# 3V3.net
KiCad netlist of a schematic drawn in Altium Designer
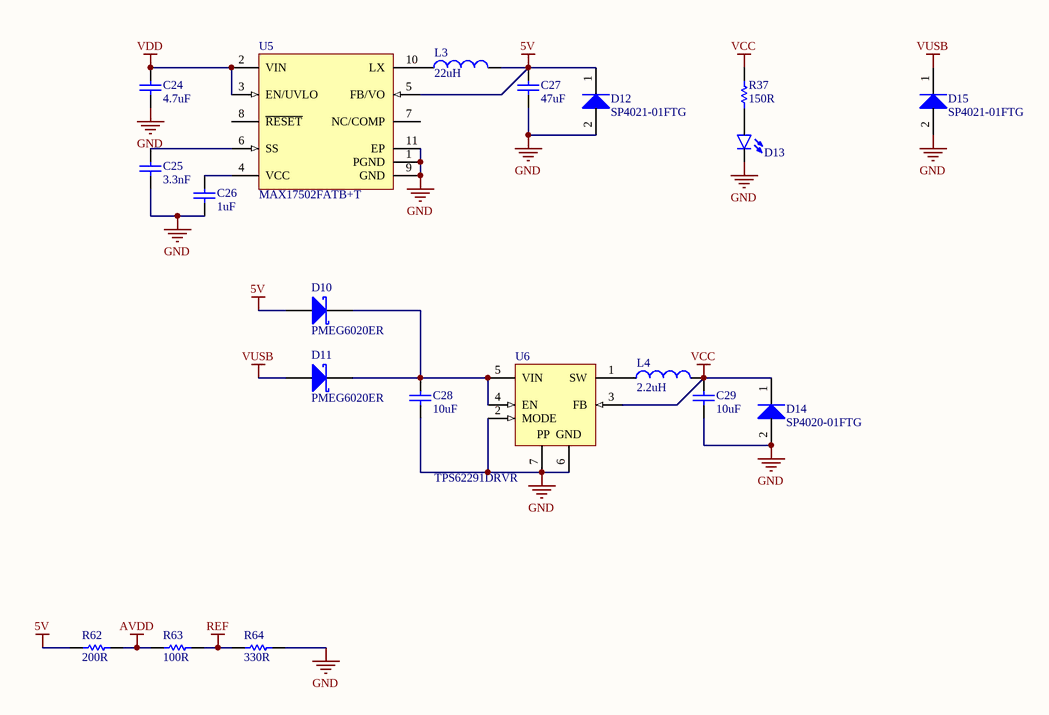
[diagram p0: 3V3.SchDoc]

(export (version "E")
  (design (tool "Eeschema 10.0.6"))
  (components
    (comp (ref "C24")
      (value "4.7uF")
      (footprint "C1210[3225X200]")
      (description "4.7uF 100V 10% 1210 (3225 Metric)")
      (fields (field (name "TOLERANCE") "10%") (field (name "PARTNUMBER") "GRJ32DC72A475KE11L"))
      (libsource (lib "Capacitors") (part "CAP_4.7uF_100V_1210_10%"))
    )
    (comp (ref "C25")
      (value "3.3nF")
      (footprint "C0402[1005X55]")
      (description "3.3nF 50V 10% 0402 (1005 Metric)")
      (fields (field (name "TOLERANCE") "10%") (field (name "PARTNUMBER") "GRM155R71H332KA01D"))
      (libsource (lib "Capacitors") (part "CAP_3.3nF_50V_0402_10%"))
    )
    (comp (ref "C26")
      (value "1uF")
      (footprint "C0402[1005X55]")
      (description "1uF 6.3V 10% 0402 (1005 Metric)")
      (fields (field (name "TOLERANCE") "10%") (field (name "PARTNUMBER") "GRM155R70J105KA12D"))
      (libsource (lib "Capacitors") (part "CAP_1uF_6.3V_0402_10%"))
    )
    (comp (ref "C27")
      (value "47uF")
      (footprint "C1210[3225X250]")
      (description "47uF 6.3V 10% 1210 (3225 Metric)")
      (fields (field (name "TOLERANCE") "10%") (field (name "PARTNUMBER") "GRM32ER70J476KE20L"))
      (libsource (lib "Capacitors") (part "CAP_47uF_6.3V_1210_10%"))
    )
    (comp (ref "C28")
      (value "10uF")
      (footprint "C0402[1005X55]")
      (description "10uF 6.3V 20% 0402 (1005 Metric)")
      (fields (field (name "TOLERANCE") "20%") (field (name "PARTNUMBER") "GRM155R60J106ME44D"))
      (libsource (lib "Capacitors") (part "CAP_10uF_6.3V_0402_20%"))
    )
    (comp (ref "C29")
      (value "10uF")
      (footprint "C0402[1005X55]")
      (description "10uF 6.3V 20% 0402 (1005 Metric)")
      (fields (field (name "TOLERANCE") "20%") (field (name "PARTNUMBER") "GRM155R60J106ME44D"))
      (libsource (lib "Capacitors") (part "CAP_10uF_6.3V_0402_20%"))
    )
    (comp (ref "D10")
      (value "PMEG6020ER")
      (footprint "SOD-123")
      (fields (field (name "PARTNUMBER") "PMEG6020ER,115") (field (name "MANUFACTURER") "NXP Semiconductors"))
      (libsource (lib "Diodes") (part "PMEG6020ER"))
    )
    (comp (ref "D11")
      (value "PMEG6020ER")
      (footprint "SOD-123")
      (fields (field (name "PARTNUMBER") "PMEG6020ER,115") (field (name "MANUFACTURER") "NXP Semiconductors"))
      (libsource (lib "Diodes") (part "PMEG6020ER"))
    )
    (comp (ref "D12")
      (value "SP4021-01FTG")
      (footprint "SOD-323")
      (fields (field (name "MANUFACTURER") "Littelfuse"))
      (libsource (lib "Diodes") (part "SP4021-01FTG"))
    )
    (comp (ref "D13")
      (value "LED_0603_GREEN_5mA")
      (footprint "LED0603")
      (fields (field (name "PARTNUMBER") "LTST-C193TGKT-5A") (field (name "MANUFACTURER") "Lite-On Inc."))
      (libsource (lib "LEDs") (part "LED_0603_GREEN_5mA"))
    )
    (comp (ref "D14")
      (value "SP4020-01FTG")
      (footprint "SOD323")
      (fields (field (name "MANUFACTURER") "Littelfuse"))
      (libsource (lib "Diodes") (part "SP4020-01FTG"))
    )
    (comp (ref "D15")
      (value "SP4021-01FTG")
      (footprint "SOD-323")
      (fields (field (name "MANUFACTURER") "Littelfuse"))
      (libsource (lib "Diodes-TVS") (part "SP4021-01FTG"))
    )
    (comp (ref "L3")
      (value "22uH")
      (footprint "SDR0604")
      (description "22uH 30% 1.1A 0604")
      (fields (field (name "PARTNUMBER") "SDR0604-220YL") (field (name "MANUFACTURER") "Bourns"))
      (libsource (lib "Inductors") (part "SDR0604-220YL"))
    )
    (comp (ref "L4")
      (value "2.2uH")
      (footprint "IND0805")
      (description "2.2uH 20% 1.7A 0805")
      (fields (field (name "PARTNUMBER") "LQM21PN2R2MGHL") (field (name "MANUFACTURER") "Murata"))
      (libsource (lib "Inductors") (part "IND_2.2uH_1.7A_0805_20%"))
    )
    (comp (ref "R37")
      (value "150R")
      (footprint "R0402[1005]")
      (description "150R 0.063W 1% 0402 (1005 Metric)")
      (fields (field (name "POWER") "0.063W") (field (name "TOLERANCE") "1%"))
      (libsource (lib "Resistors") (part "RES_150R_0402_1%"))
    )
    (comp (ref "R62")
      (value "200R")
      (footprint "R0603[1608]")
      (description "200R 0.25W 1% 0603 (1005 Metric)")
      (fields (field (name "MANUFACTURER") "Vishay / Dale") (field (name "TOLERANCE") "1%"))
      (libsource (lib "Resistors") (part "RES_200R_0603_1%"))
    )
    (comp (ref "R63")
      (value "100R")
      (footprint "R0603[1608]")
      (description "100R 0.25W 1% 0603 (1005 Metric)")
      (fields (field (name "MANUFACTURER") "Vishay / Dale") (field (name "TOLERANCE") "1%"))
      (libsource (lib "Resistors") (part "RES_100R_0603_1%"))
    )
    (comp (ref "R64")
      (value "330R")
      (footprint "R0603[1608]")
      (description "330R 0.25W 1% 0603 (1005 Metric)")
      (fields (field (name "MANUFACTURER") "Vishay / Dale") (field (name "TOLERANCE") "1%"))
      (libsource (lib "Resistors") (part "RES_330R_0603_1%"))
    )
    (comp (ref "U5")
      (value "MAX17502FATB+T")
      (footprint "TDFN-10-EP")
      (fields (field (name "MANUFACTURER") "Maxim Integrated"))
      (libsource (lib "ICs") (part "MAX17502FATB+T"))
    )
    (comp (ref "U6")
      (value "TPS62291DRVR")
      (footprint "WSON-6")
      (description "Voltage Regulators - Switching Regulators 2.25MHz 1A Step-Down Cnvrtr 3.3V Output")
      (fields (field (name "MANUFACTURER") "Texas Instruments"))
      (libsource (lib "ICs") (part "TPS62291DRVR"))
    )
  )
  (nets
    (net (code "1") (name "5V") (class "Default")
      (node (ref "C27") (pin "2") (pinfunction "2_2") (pintype "passive"))
      (node (ref "D10") (pin "2") (pinfunction "A_2") (pintype "passive"))
      (node (ref "D12") (pin "1") (pinfunction "K_1") (pintype "passive"))
      (node (ref "L3") (pin "2") (pinfunction "2_2") (pintype "passive"))
      (node (ref "R62") (pin "1") (pinfunction "1_1") (pintype "passive"))
      (node (ref "U5") (pin "5") (pinfunction "FB/VO_5") (pintype "input"))
    )
    (net (code "2") (name "AVDD") (class "Default")
      (node (ref "R62") (pin "2") (pinfunction "2_2") (pintype "passive"))
      (node (ref "R63") (pin "1") (pinfunction "1_1") (pintype "passive"))
    )
    (net (code "3") (name "GND") (class "Default")
      (node (ref "C24") (pin "1") (pinfunction "1_1") (pintype "passive"))
      (node (ref "C25") (pin "1") (pinfunction "1_1") (pintype "passive"))
      (node (ref "C26") (pin "1") (pinfunction "1_1") (pintype "passive"))
      (node (ref "C27") (pin "1") (pinfunction "1_1") (pintype "passive"))
      (node (ref "C28") (pin "1") (pinfunction "1_1") (pintype "passive"))
      (node (ref "C29") (pin "1") (pinfunction "1_1") (pintype "passive"))
      (node (ref "D12") (pin "2") (pinfunction "A_2") (pintype "passive"))
      (node (ref "D13") (pin "C") (pinfunction "C_C") (pintype "passive"))
      (node (ref "D14") (pin "2") (pinfunction "A_2") (pintype "passive"))
      (node (ref "D15") (pin "2") (pinfunction "A_2") (pintype "passive"))
      (node (ref "R64") (pin "2") (pinfunction "2_2") (pintype "passive"))
      (node (ref "U5") (pin "1") (pinfunction "PGND_1") (pintype "power_in"))
      (node (ref "U5") (pin "11") (pinfunction "EP_11") (pintype "power_in"))
      (node (ref "U5") (pin "9") (pinfunction "GND_9") (pintype "power_in"))
      (node (ref "U6") (pin "2") (pinfunction "MODE_2") (pintype "input"))
      (node (ref "U6") (pin "6") (pinfunction "GND_6") (pintype "power_in"))
      (node (ref "U6") (pin "7") (pinfunction "EP_7") (pintype "passive"))
    )
    (net (code "4") (name "Net-(D10-K)") (class "Default")
      (node (ref "C28") (pin "2") (pinfunction "2_2") (pintype "passive"))
      (node (ref "D10") (pin "1") (pinfunction "K_1") (pintype "passive"))
      (node (ref "D11") (pin "1") (pinfunction "K_1") (pintype "passive"))
      (node (ref "U6") (pin "4") (pinfunction "EN_4") (pintype "input"))
      (node (ref "U6") (pin "5") (pinfunction "VIN_5") (pintype "power_in"))
    )
    (net (code "5") (name "Net-(D13-PadA)") (class "Default")
      (node (ref "D13") (pin "A") (pinfunction "A_A") (pintype "passive"))
      (node (ref "R37") (pin "1") (pinfunction "1_1") (pintype "passive"))
    )
    (net (code "6") (name "Net-(U5-LX)") (class "Default")
      (node (ref "L3") (pin "1") (pinfunction "1_1") (pintype "passive"))
      (node (ref "U5") (pin "10") (pinfunction "LX_10") (pintype "passive"))
    )
    (net (code "7") (name "Net-(U5-SS)") (class "Default")
      (node (ref "C25") (pin "2") (pinfunction "2_2") (pintype "passive"))
      (node (ref "U5") (pin "6") (pinfunction "SS_6") (pintype "input"))
    )
    (net (code "8") (name "Net-(U5-VCC)") (class "Default")
      (node (ref "C26") (pin "2") (pinfunction "2_2") (pintype "passive"))
      (node (ref "U5") (pin "4") (pinfunction "VCC_4") (pintype "power_in"))
    )
    (net (code "9") (name "Net-(U6-SW)") (class "Default")
      (node (ref "L4") (pin "1") (pinfunction "1_1") (pintype "passive"))
      (node (ref "U6") (pin "1") (pinfunction "SW_1") (pintype "power_in"))
    )
    (net (code "10") (name "REF") (class "Default")
      (node (ref "R63") (pin "2") (pinfunction "2_2") (pintype "passive"))
      (node (ref "R64") (pin "1") (pinfunction "1_1") (pintype "passive"))
    )
    (net (code "11") (name "VCC") (class "Default")
      (node (ref "C29") (pin "2") (pinfunction "2_2") (pintype "passive"))
      (node (ref "D14") (pin "1") (pinfunction "K_1") (pintype "passive"))
      (node (ref "L4") (pin "2") (pinfunction "2_2") (pintype "passive"))
      (node (ref "R37") (pin "2") (pinfunction "2_2") (pintype "passive"))
      (node (ref "U6") (pin "3") (pinfunction "FB_3") (pintype "input"))
    )
    (net (code "12") (name "VDD") (class "Default")
      (node (ref "C24") (pin "2") (pinfunction "2_2") (pintype "passive"))
      (node (ref "U5") (pin "2") (pinfunction "VIN_2") (pintype "power_in"))
      (node (ref "U5") (pin "3") (pinfunction "EN/UVLO_3") (pintype "input"))
    )
    (net (code "13") (name "VUSB") (class "Default")
      (node (ref "D11") (pin "2") (pinfunction "A_2") (pintype "passive"))
      (node (ref "D15") (pin "1") (pinfunction "K_1") (pintype "passive"))
    )
    (net (code "14") (name "unconnected-(U5-NC{slash}COMP-Pad7)") (class "Default")
      (node (ref "U5") (pin "7") (pinfunction "NC/COMP_7") (pintype "passive"))
    )
    (net (code "15") (name "unconnected-(U5-~{RESET}-Pad8)") (class "Default")
      (node (ref "U5") (pin "8") (pinfunction "~{RESET}_8") (pintype "open_collector"))
    )
  )
)
